# FPGA1_POWER.net
KiCad netlist of a schematic drawn in Altium Designer
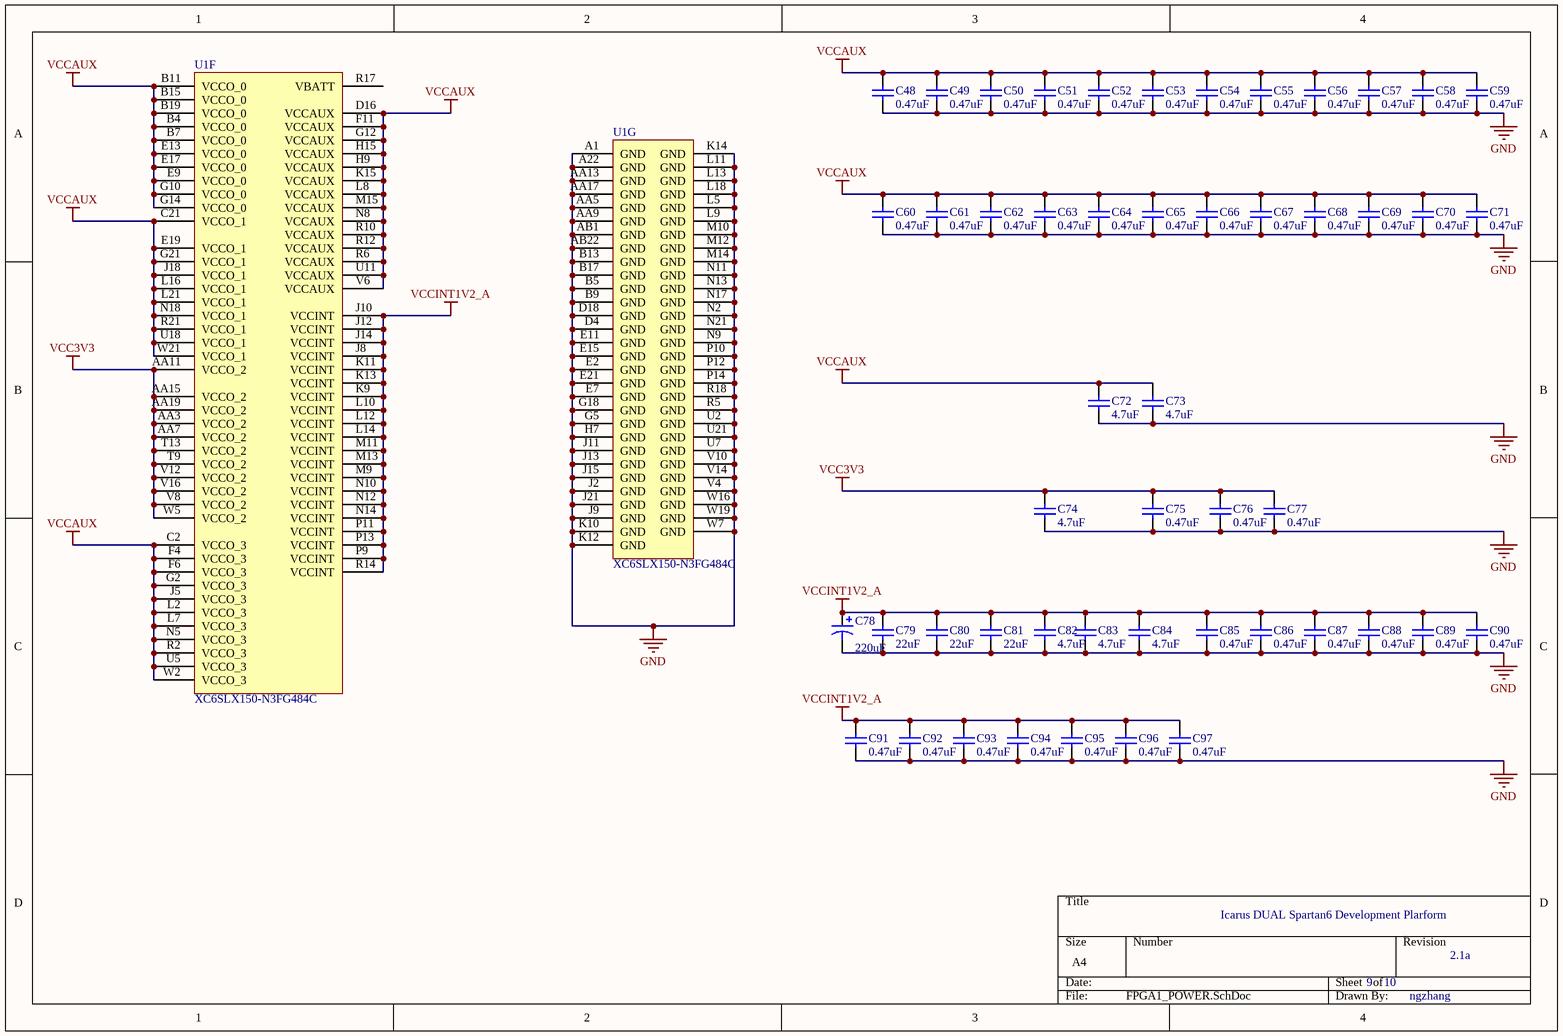
[diagram p0: FPGA1_POWER.SchDoc]

(export (version "E")
  (design (tool "Eeschema 10.0.6"))
  (components
    (comp (ref "C48")
      (value "0.47uF")
      (footprint "0402")
      (description "Capacitor (Semiconductor SIM Model)")
      (fields (field (name "PUBLISHER") "Altium Limited"))
      (libsource (lib "Miscellaneous Devices") (part "Cap Semi"))
    )
    (comp (ref "C49")
      (value "0.47uF")
      (footprint "0402")
      (description "Capacitor (Semiconductor SIM Model)")
      (fields (field (name "PUBLISHER") "Altium Limited"))
      (libsource (lib "Miscellaneous Devices") (part "Cap Semi"))
    )
    (comp (ref "C50")
      (value "0.47uF")
      (footprint "0402")
      (description "Capacitor (Semiconductor SIM Model)")
      (fields (field (name "PUBLISHER") "Altium Limited"))
      (libsource (lib "Miscellaneous Devices") (part "Cap Semi"))
    )
    (comp (ref "C51")
      (value "0.47uF")
      (footprint "0402")
      (description "Capacitor (Semiconductor SIM Model)")
      (fields (field (name "PUBLISHER") "Altium Limited"))
      (libsource (lib "Miscellaneous Devices") (part "Cap Semi"))
    )
    (comp (ref "C52")
      (value "0.47uF")
      (footprint "0402")
      (description "Capacitor (Semiconductor SIM Model)")
      (fields (field (name "PUBLISHER") "Altium Limited"))
      (libsource (lib "Miscellaneous Devices") (part "Cap Semi"))
    )
    (comp (ref "C53")
      (value "0.47uF")
      (footprint "0402")
      (description "Capacitor (Semiconductor SIM Model)")
      (fields (field (name "PUBLISHER") "Altium Limited"))
      (libsource (lib "Miscellaneous Devices") (part "Cap Semi"))
    )
    (comp (ref "C54")
      (value "0.47uF")
      (footprint "0402")
      (description "Capacitor (Semiconductor SIM Model)")
      (fields (field (name "PUBLISHER") "Altium Limited"))
      (libsource (lib "Miscellaneous Devices") (part "Cap Semi"))
    )
    (comp (ref "C55")
      (value "0.47uF")
      (footprint "0402")
      (description "Capacitor (Semiconductor SIM Model)")
      (fields (field (name "PUBLISHER") "Altium Limited"))
      (libsource (lib "Miscellaneous Devices") (part "Cap Semi"))
    )
    (comp (ref "C56")
      (value "0.47uF")
      (footprint "0402")
      (description "Capacitor (Semiconductor SIM Model)")
      (fields (field (name "PUBLISHER") "Altium Limited"))
      (libsource (lib "Miscellaneous Devices") (part "Cap Semi"))
    )
    (comp (ref "C57")
      (value "0.47uF")
      (footprint "0402")
      (description "Capacitor (Semiconductor SIM Model)")
      (fields (field (name "PUBLISHER") "Altium Limited"))
      (libsource (lib "Miscellaneous Devices") (part "Cap Semi"))
    )
    (comp (ref "C58")
      (value "0.47uF")
      (footprint "0402")
      (description "Capacitor (Semiconductor SIM Model)")
      (fields (field (name "PUBLISHER") "Altium Limited"))
      (libsource (lib "Miscellaneous Devices") (part "Cap Semi"))
    )
    (comp (ref "C59")
      (value "0.47uF")
      (footprint "0402")
      (description "Capacitor (Semiconductor SIM Model)")
      (fields (field (name "PUBLISHER") "Altium Limited"))
      (libsource (lib "Miscellaneous Devices") (part "Cap Semi"))
    )
    (comp (ref "C60")
      (value "0.47uF")
      (footprint "0402")
      (description "Capacitor (Semiconductor SIM Model)")
      (fields (field (name "PUBLISHER") "Altium Limited"))
      (libsource (lib "Miscellaneous Devices") (part "Cap Semi"))
    )
    (comp (ref "C61")
      (value "0.47uF")
      (footprint "0402")
      (description "Capacitor (Semiconductor SIM Model)")
      (fields (field (name "PUBLISHER") "Altium Limited"))
      (libsource (lib "Miscellaneous Devices") (part "Cap Semi"))
    )
    (comp (ref "C62")
      (value "0.47uF")
      (footprint "0402")
      (description "Capacitor (Semiconductor SIM Model)")
      (fields (field (name "PUBLISHER") "Altium Limited"))
      (libsource (lib "Miscellaneous Devices") (part "Cap Semi"))
    )
    (comp (ref "C63")
      (value "0.47uF")
      (footprint "0402")
      (description "Capacitor (Semiconductor SIM Model)")
      (fields (field (name "PUBLISHER") "Altium Limited"))
      (libsource (lib "Miscellaneous Devices") (part "Cap Semi"))
    )
    (comp (ref "C64")
      (value "0.47uF")
      (footprint "0402")
      (description "Capacitor (Semiconductor SIM Model)")
      (fields (field (name "PUBLISHER") "Altium Limited"))
      (libsource (lib "Miscellaneous Devices") (part "Cap Semi"))
    )
    (comp (ref "C65")
      (value "0.47uF")
      (footprint "0402")
      (description "Capacitor (Semiconductor SIM Model)")
      (fields (field (name "PUBLISHER") "Altium Limited"))
      (libsource (lib "Miscellaneous Devices") (part "Cap Semi"))
    )
    (comp (ref "C66")
      (value "0.47uF")
      (footprint "0402")
      (description "Capacitor (Semiconductor SIM Model)")
      (fields (field (name "PUBLISHER") "Altium Limited"))
      (libsource (lib "Miscellaneous Devices") (part "Cap Semi"))
    )
    (comp (ref "C67")
      (value "0.47uF")
      (footprint "0402")
      (description "Capacitor (Semiconductor SIM Model)")
      (fields (field (name "PUBLISHER") "Altium Limited"))
      (libsource (lib "Miscellaneous Devices") (part "Cap Semi"))
    )
    (comp (ref "C68")
      (value "0.47uF")
      (footprint "0402")
      (description "Capacitor (Semiconductor SIM Model)")
      (fields (field (name "PUBLISHER") "Altium Limited"))
      (libsource (lib "Miscellaneous Devices") (part "Cap Semi"))
    )
    (comp (ref "C69")
      (value "0.47uF")
      (footprint "0402")
      (description "Capacitor (Semiconductor SIM Model)")
      (fields (field (name "PUBLISHER") "Altium Limited"))
      (libsource (lib "Miscellaneous Devices") (part "Cap Semi"))
    )
    (comp (ref "C70")
      (value "0.47uF")
      (footprint "0402")
      (description "Capacitor (Semiconductor SIM Model)")
      (fields (field (name "PUBLISHER") "Altium Limited"))
      (libsource (lib "Miscellaneous Devices") (part "Cap Semi"))
    )
    (comp (ref "C71")
      (value "0.47uF")
      (footprint "0402")
      (description "Capacitor (Semiconductor SIM Model)")
      (fields (field (name "PUBLISHER") "Altium Limited"))
      (libsource (lib "Miscellaneous Devices") (part "Cap Semi"))
    )
    (comp (ref "C72")
      (value "4.7uF")
      (footprint "C0805")
      (description "Capacitor (Semiconductor SIM Model)")
      (fields (field (name "PUBLISHER") "Altium Limited"))
      (libsource (lib "Miscellaneous Devices") (part "Cap Semi"))
    )
    (comp (ref "C73")
      (value "4.7uF")
      (footprint "C0805")
      (description "Capacitor (Semiconductor SIM Model)")
      (fields (field (name "PUBLISHER") "Altium Limited"))
      (libsource (lib "Miscellaneous Devices") (part "Cap Semi"))
    )
    (comp (ref "C74")
      (value "4.7uF")
      (footprint "C0805")
      (description "Capacitor (Semiconductor SIM Model)")
      (fields (field (name "PUBLISHER") "Altium Limited"))
      (libsource (lib "Miscellaneous Devices") (part "Cap Semi"))
    )
    (comp (ref "C75")
      (value "0.47uF")
      (footprint "0402")
      (description "Capacitor (Semiconductor SIM Model)")
      (fields (field (name "PUBLISHER") "Altium Limited"))
      (libsource (lib "Miscellaneous Devices") (part "Cap Semi"))
    )
    (comp (ref "C76")
      (value "0.47uF")
      (footprint "0402")
      (description "Capacitor (Semiconductor SIM Model)")
      (fields (field (name "PUBLISHER") "Altium Limited"))
      (libsource (lib "Miscellaneous Devices") (part "Cap Semi"))
    )
    (comp (ref "C77")
      (value "0.47uF")
      (footprint "0402")
      (description "Capacitor (Semiconductor SIM Model)")
      (fields (field (name "PUBLISHER") "Altium Limited"))
      (libsource (lib "Miscellaneous Devices") (part "Cap Semi"))
    )
    (comp (ref "C78")
      (value "220uF")
      (footprint "D")
      (description "Polarized Capacitor (Surface Mount)")
      (fields (field (name "PUBLISHER") "Altium Limited"))
      (libsource (lib "Miscellaneous Devices") (part "Cap Pol3"))
    )
    (comp (ref "C79")
      (value "22uF")
      (footprint "C1206")
      (description "Capacitor (Semiconductor SIM Model)")
      (fields (field (name "PUBLISHER") "Altium Limited"))
      (libsource (lib "Miscellaneous Devices") (part "Cap Semi"))
    )
    (comp (ref "C80")
      (value "22uF")
      (footprint "C1206")
      (description "Capacitor (Semiconductor SIM Model)")
      (fields (field (name "PUBLISHER") "Altium Limited"))
      (libsource (lib "Miscellaneous Devices") (part "Cap Semi"))
    )
    (comp (ref "C81")
      (value "22uF")
      (footprint "C1206")
      (description "Capacitor (Semiconductor SIM Model)")
      (fields (field (name "PUBLISHER") "Altium Limited"))
      (libsource (lib "Miscellaneous Devices") (part "Cap Semi"))
    )
    (comp (ref "C82")
      (value "4.7uF")
      (footprint "C0805")
      (description "Capacitor (Semiconductor SIM Model)")
      (fields (field (name "PUBLISHER") "Altium Limited"))
      (libsource (lib "Miscellaneous Devices") (part "Cap Semi"))
    )
    (comp (ref "C83")
      (value "4.7uF")
      (footprint "C0805")
      (description "Capacitor (Semiconductor SIM Model)")
      (fields (field (name "PUBLISHER") "Altium Limited"))
      (libsource (lib "Miscellaneous Devices") (part "Cap Semi"))
    )
    (comp (ref "C84")
      (value "4.7uF")
      (footprint "C0805")
      (description "Capacitor (Semiconductor SIM Model)")
      (fields (field (name "PUBLISHER") "Altium Limited"))
      (libsource (lib "Miscellaneous Devices") (part "Cap Semi"))
    )
    (comp (ref "C85")
      (value "0.47uF")
      (footprint "0402")
      (description "Capacitor (Semiconductor SIM Model)")
      (fields (field (name "PUBLISHER") "Altium Limited"))
      (libsource (lib "Miscellaneous Devices") (part "Cap Semi"))
    )
    (comp (ref "C86")
      (value "0.47uF")
      (footprint "0402")
      (description "Capacitor (Semiconductor SIM Model)")
      (fields (field (name "PUBLISHER") "Altium Limited"))
      (libsource (lib "Miscellaneous Devices") (part "Cap Semi"))
    )
    (comp (ref "C87")
      (value "0.47uF")
      (footprint "0402")
      (description "Capacitor (Semiconductor SIM Model)")
      (fields (field (name "PUBLISHER") "Altium Limited"))
      (libsource (lib "Miscellaneous Devices") (part "Cap Semi"))
    )
    (comp (ref "C88")
      (value "0.47uF")
      (footprint "0402")
      (description "Capacitor (Semiconductor SIM Model)")
      (fields (field (name "PUBLISHER") "Altium Limited"))
      (libsource (lib "Miscellaneous Devices") (part "Cap Semi"))
    )
    (comp (ref "C89")
      (value "0.47uF")
      (footprint "0402")
      (description "Capacitor (Semiconductor SIM Model)")
      (fields (field (name "PUBLISHER") "Altium Limited"))
      (libsource (lib "Miscellaneous Devices") (part "Cap Semi"))
    )
    (comp (ref "C90")
      (value "0.47uF")
      (footprint "0402")
      (description "Capacitor (Semiconductor SIM Model)")
      (fields (field (name "PUBLISHER") "Altium Limited"))
      (libsource (lib "Miscellaneous Devices") (part "Cap Semi"))
    )
    (comp (ref "C91")
      (value "0.47uF")
      (footprint "0402")
      (description "Capacitor (Semiconductor SIM Model)")
      (fields (field (name "PUBLISHER") "Altium Limited"))
      (libsource (lib "Miscellaneous Devices") (part "Cap Semi"))
    )
    (comp (ref "C92")
      (value "0.47uF")
      (footprint "0402")
      (description "Capacitor (Semiconductor SIM Model)")
      (fields (field (name "PUBLISHER") "Altium Limited"))
      (libsource (lib "Miscellaneous Devices") (part "Cap Semi"))
    )
    (comp (ref "C93")
      (value "0.47uF")
      (footprint "0402")
      (description "Capacitor (Semiconductor SIM Model)")
      (fields (field (name "PUBLISHER") "Altium Limited"))
      (libsource (lib "Miscellaneous Devices") (part "Cap Semi"))
    )
    (comp (ref "C94")
      (value "0.47uF")
      (footprint "0402")
      (description "Capacitor (Semiconductor SIM Model)")
      (fields (field (name "PUBLISHER") "Altium Limited"))
      (libsource (lib "Miscellaneous Devices") (part "Cap Semi"))
    )
    (comp (ref "C95")
      (value "0.47uF")
      (footprint "0402")
      (description "Capacitor (Semiconductor SIM Model)")
      (fields (field (name "PUBLISHER") "Altium Limited"))
      (libsource (lib "Miscellaneous Devices") (part "Cap Semi"))
    )
    (comp (ref "C96")
      (value "0.47uF")
      (footprint "0402")
      (description "Capacitor (Semiconductor SIM Model)")
      (fields (field (name "PUBLISHER") "Altium Limited"))
      (libsource (lib "Miscellaneous Devices") (part "Cap Semi"))
    )
    (comp (ref "C97")
      (value "0.47uF")
      (footprint "0402")
      (description "Capacitor (Semiconductor SIM Model)")
      (fields (field (name "PUBLISHER") "Altium Limited"))
      (libsource (lib "Miscellaneous Devices") (part "Cap Semi"))
    )
    (comp (ref "U1")
      (value "XC6SLX150-N3FG484C")
      (footprint "FG484")
      (fields (field (name "PUBLISHER") "Altium Limited"))
      (libsource (lib "Xilinx Spartan-6") (part "XC6SLX150-N3FG484C"))
    )
  )
  (nets
    (net (code "1") (name "GND") (class "Default")
      (node (ref "C48") (pin "1") (pinfunction "1_1") (pintype "passive"))
      (node (ref "C49") (pin "1") (pinfunction "1_1") (pintype "passive"))
      (node (ref "C50") (pin "1") (pinfunction "1_1") (pintype "passive"))
      (node (ref "C51") (pin "1") (pinfunction "1_1") (pintype "passive"))
      (node (ref "C52") (pin "1") (pinfunction "1_1") (pintype "passive"))
      (node (ref "C53") (pin "1") (pinfunction "1_1") (pintype "passive"))
      (node (ref "C54") (pin "1") (pinfunction "1_1") (pintype "passive"))
      (node (ref "C55") (pin "1") (pinfunction "1_1") (pintype "passive"))
      (node (ref "C56") (pin "1") (pinfunction "1_1") (pintype "passive"))
      (node (ref "C57") (pin "1") (pinfunction "1_1") (pintype "passive"))
      (node (ref "C58") (pin "1") (pinfunction "1_1") (pintype "passive"))
      (node (ref "C59") (pin "1") (pinfunction "1_1") (pintype "passive"))
      (node (ref "C60") (pin "1") (pinfunction "1_1") (pintype "passive"))
      (node (ref "C61") (pin "1") (pinfunction "1_1") (pintype "passive"))
      (node (ref "C62") (pin "1") (pinfunction "1_1") (pintype "passive"))
      (node (ref "C63") (pin "1") (pinfunction "1_1") (pintype "passive"))
      (node (ref "C64") (pin "1") (pinfunction "1_1") (pintype "passive"))
      (node (ref "C65") (pin "1") (pinfunction "1_1") (pintype "passive"))
      (node (ref "C66") (pin "1") (pinfunction "1_1") (pintype "passive"))
      (node (ref "C67") (pin "1") (pinfunction "1_1") (pintype "passive"))
      (node (ref "C68") (pin "1") (pinfunction "1_1") (pintype "passive"))
      (node (ref "C69") (pin "1") (pinfunction "1_1") (pintype "passive"))
      (node (ref "C70") (pin "1") (pinfunction "1_1") (pintype "passive"))
      (node (ref "C71") (pin "1") (pinfunction "1_1") (pintype "passive"))
      (node (ref "C72") (pin "1") (pinfunction "1_1") (pintype "passive"))
      (node (ref "C73") (pin "1") (pinfunction "1_1") (pintype "passive"))
      (node (ref "C74") (pin "1") (pinfunction "1_1") (pintype "passive"))
      (node (ref "C75") (pin "1") (pinfunction "1_1") (pintype "passive"))
      (node (ref "C76") (pin "1") (pinfunction "1_1") (pintype "passive"))
      (node (ref "C77") (pin "1") (pinfunction "1_1") (pintype "passive"))
      (node (ref "C78") (pin "2") (pinfunction "2_2") (pintype "passive"))
      (node (ref "C79") (pin "1") (pinfunction "1_1") (pintype "passive"))
      (node (ref "C80") (pin "1") (pinfunction "1_1") (pintype "passive"))
      (node (ref "C81") (pin "1") (pinfunction "1_1") (pintype "passive"))
      (node (ref "C82") (pin "1") (pinfunction "1_1") (pintype "passive"))
      (node (ref "C83") (pin "1") (pinfunction "1_1") (pintype "passive"))
      (node (ref "C84") (pin "1") (pinfunction "1_1") (pintype "passive"))
      (node (ref "C85") (pin "1") (pinfunction "1_1") (pintype "passive"))
      (node (ref "C86") (pin "1") (pinfunction "1_1") (pintype "passive"))
      (node (ref "C87") (pin "1") (pinfunction "1_1") (pintype "passive"))
      (node (ref "C88") (pin "1") (pinfunction "1_1") (pintype "passive"))
      (node (ref "C89") (pin "1") (pinfunction "1_1") (pintype "passive"))
      (node (ref "C90") (pin "1") (pinfunction "1_1") (pintype "passive"))
      (node (ref "C91") (pin "1") (pinfunction "1_1") (pintype "passive"))
      (node (ref "C92") (pin "1") (pinfunction "1_1") (pintype "passive"))
      (node (ref "C93") (pin "1") (pinfunction "1_1") (pintype "passive"))
      (node (ref "C94") (pin "1") (pinfunction "1_1") (pintype "passive"))
      (node (ref "C95") (pin "1") (pinfunction "1_1") (pintype "passive"))
      (node (ref "C96") (pin "1") (pinfunction "1_1") (pintype "passive"))
      (node (ref "C97") (pin "1") (pinfunction "1_1") (pintype "passive"))
      (node (ref "U1") (pin "A1") (pinfunction "GND_A1") (pintype "power_in"))
      (node (ref "U1") (pin "A22") (pinfunction "GND_A22") (pintype "power_in"))
      (node (ref "U1") (pin "AA13") (pinfunction "GND_AA13") (pintype "power_in"))
      (node (ref "U1") (pin "AA17") (pinfunction "GND_AA17") (pintype "power_in"))
      (node (ref "U1") (pin "AA5") (pinfunction "GND_AA5") (pintype "power_in"))
      (node (ref "U1") (pin "AA9") (pinfunction "GND_AA9") (pintype "power_in"))
      (node (ref "U1") (pin "AB1") (pinfunction "GND_AB1") (pintype "power_in"))
      (node (ref "U1") (pin "AB22") (pinfunction "GND_AB22") (pintype "power_in"))
      (node (ref "U1") (pin "B13") (pinfunction "GND_B13") (pintype "power_in"))
      (node (ref "U1") (pin "B17") (pinfunction "GND_B17") (pintype "power_in"))
      (node (ref "U1") (pin "B5") (pinfunction "GND_B5") (pintype "power_in"))
      (node (ref "U1") (pin "B9") (pinfunction "GND_B9") (pintype "power_in"))
      (node (ref "U1") (pin "D18") (pinfunction "GND_D18") (pintype "power_in"))
      (node (ref "U1") (pin "D4") (pinfunction "GND_D4") (pintype "power_in"))
      (node (ref "U1") (pin "E11") (pinfunction "GND_E11") (pintype "power_in"))
      (node (ref "U1") (pin "E15") (pinfunction "GND_E15") (pintype "power_in"))
      (node (ref "U1") (pin "E2") (pinfunction "GND_E2") (pintype "power_in"))
      (node (ref "U1") (pin "E21") (pinfunction "GND_E21") (pintype "power_in"))
      (node (ref "U1") (pin "E7") (pinfunction "GND_E7") (pintype "power_in"))
      (node (ref "U1") (pin "G18") (pinfunction "GND_G18") (pintype "power_in"))
      (node (ref "U1") (pin "G5") (pinfunction "GND_G5") (pintype "power_in"))
      (node (ref "U1") (pin "H7") (pinfunction "GND_H7") (pintype "power_in"))
      (node (ref "U1") (pin "J11") (pinfunction "GND_J11") (pintype "power_in"))
      (node (ref "U1") (pin "J13") (pinfunction "GND_J13") (pintype "power_in"))
      (node (ref "U1") (pin "J15") (pinfunction "GND_J15") (pintype "power_in"))
      (node (ref "U1") (pin "J2") (pinfunction "GND_J2") (pintype "power_in"))
      (node (ref "U1") (pin "J21") (pinfunction "GND_J21") (pintype "power_in"))
      (node (ref "U1") (pin "J9") (pinfunction "GND_J9") (pintype "power_in"))
      (node (ref "U1") (pin "K10") (pinfunction "GND_K10") (pintype "power_in"))
      (node (ref "U1") (pin "K12") (pinfunction "GND_K12") (pintype "power_in"))
      (node (ref "U1") (pin "K14") (pinfunction "GND_K14") (pintype "power_in"))
      (node (ref "U1") (pin "L11") (pinfunction "GND_L11") (pintype "power_in"))
      (node (ref "U1") (pin "L13") (pinfunction "GND_L13") (pintype "power_in"))
      (node (ref "U1") (pin "L18") (pinfunction "GND_L18") (pintype "power_in"))
      (node (ref "U1") (pin "L5") (pinfunction "GND_L5") (pintype "power_in"))
      (node (ref "U1") (pin "L9") (pinfunction "GND_L9") (pintype "power_in"))
      (node (ref "U1") (pin "M10") (pinfunction "GND_M10") (pintype "power_in"))
      (node (ref "U1") (pin "M12") (pinfunction "GND_M12") (pintype "power_in"))
      (node (ref "U1") (pin "M14") (pinfunction "GND_M14") (pintype "power_in"))
      (node (ref "U1") (pin "N11") (pinfunction "GND_N11") (pintype "power_in"))
      (node (ref "U1") (pin "N13") (pinfunction "GND_N13") (pintype "power_in"))
      (node (ref "U1") (pin "N17") (pinfunction "GND_N17") (pintype "power_in"))
      (node (ref "U1") (pin "N2") (pinfunction "GND_N2") (pintype "power_in"))
      (node (ref "U1") (pin "N21") (pinfunction "GND_N21") (pintype "power_in"))
      (node (ref "U1") (pin "N9") (pinfunction "GND_N9") (pintype "power_in"))
      (node (ref "U1") (pin "P10") (pinfunction "GND_P10") (pintype "power_in"))
      (node (ref "U1") (pin "P12") (pinfunction "GND_P12") (pintype "power_in"))
      (node (ref "U1") (pin "P14") (pinfunction "GND_P14") (pintype "power_in"))
      (node (ref "U1") (pin "R18") (pinfunction "GND_R18") (pintype "power_in"))
      (node (ref "U1") (pin "R5") (pinfunction "GND_R5") (pintype "power_in"))
      (node (ref "U1") (pin "U2") (pinfunction "GND_U2") (pintype "power_in"))
      (node (ref "U1") (pin "U21") (pinfunction "GND_U21") (pintype "power_in"))
      (node (ref "U1") (pin "U7") (pinfunction "GND_U7") (pintype "power_in"))
      (node (ref "U1") (pin "V10") (pinfunction "GND_V10") (pintype "power_in"))
      (node (ref "U1") (pin "V14") (pinfunction "GND_V14") (pintype "power_in"))
      (node (ref "U1") (pin "V4") (pinfunction "GND_V4") (pintype "power_in"))
      (node (ref "U1") (pin "W16") (pinfunction "GND_W16") (pintype "power_in"))
      (node (ref "U1") (pin "W19") (pinfunction "GND_W19") (pintype "power_in"))
      (node (ref "U1") (pin "W7") (pinfunction "GND_W7") (pintype "power_in"))
    )
    (net (code "2") (name "VCC3V3") (class "Default")
      (node (ref "C74") (pin "2") (pinfunction "2_2") (pintype "passive"))
      (node (ref "C75") (pin "2") (pinfunction "2_2") (pintype "passive"))
      (node (ref "C76") (pin "2") (pinfunction "2_2") (pintype "passive"))
      (node (ref "C77") (pin "2") (pinfunction "2_2") (pintype "passive"))
      (node (ref "U1") (pin "AA11") (pinfunction "VCCO_2_AA11") (pintype "power_in"))
      (node (ref "U1") (pin "AA15") (pinfunction "VCCO_2_AA15") (pintype "power_in"))
      (node (ref "U1") (pin "AA19") (pinfunction "VCCO_2_AA19") (pintype "power_in"))
      (node (ref "U1") (pin "AA3") (pinfunction "VCCO_2_AA3") (pintype "power_in"))
      (node (ref "U1") (pin "AA7") (pinfunction "VCCO_2_AA7") (pintype "power_in"))
      (node (ref "U1") (pin "T13") (pinfunction "VCCO_2_T13") (pintype "power_in"))
      (node (ref "U1") (pin "T9") (pinfunction "VCCO_2_T9") (pintype "power_in"))
      (node (ref "U1") (pin "V12") (pinfunction "VCCO_2_V12") (pintype "power_in"))
      (node (ref "U1") (pin "V16") (pinfunction "VCCO_2_V16") (pintype "power_in"))
      (node (ref "U1") (pin "V8") (pinfunction "VCCO_2_V8") (pintype "power_in"))
      (node (ref "U1") (pin "W5") (pinfunction "VCCO_2_W5") (pintype "power_in"))
    )
    (net (code "3") (name "VCCAUX") (class "Default")
      (node (ref "C48") (pin "2") (pinfunction "2_2") (pintype "passive"))
      (node (ref "C49") (pin "2") (pinfunction "2_2") (pintype "passive"))
      (node (ref "C50") (pin "2") (pinfunction "2_2") (pintype "passive"))
      (node (ref "C51") (pin "2") (pinfunction "2_2") (pintype "passive"))
      (node (ref "C52") (pin "2") (pinfunction "2_2") (pintype "passive"))
      (node (ref "C53") (pin "2") (pinfunction "2_2") (pintype "passive"))
      (node (ref "C54") (pin "2") (pinfunction "2_2") (pintype "passive"))
      (node (ref "C55") (pin "2") (pinfunction "2_2") (pintype "passive"))
      (node (ref "C56") (pin "2") (pinfunction "2_2") (pintype "passive"))
      (node (ref "C57") (pin "2") (pinfunction "2_2") (pintype "passive"))
      (node (ref "C58") (pin "2") (pinfunction "2_2") (pintype "passive"))
      (node (ref "C59") (pin "2") (pinfunction "2_2") (pintype "passive"))
      (node (ref "C60") (pin "2") (pinfunction "2_2") (pintype "passive"))
      (node (ref "C61") (pin "2") (pinfunction "2_2") (pintype "passive"))
      (node (ref "C62") (pin "2") (pinfunction "2_2") (pintype "passive"))
      (node (ref "C63") (pin "2") (pinfunction "2_2") (pintype "passive"))
      (node (ref "C64") (pin "2") (pinfunction "2_2") (pintype "passive"))
      (node (ref "C65") (pin "2") (pinfunction "2_2") (pintype "passive"))
      (node (ref "C66") (pin "2") (pinfunction "2_2") (pintype "passive"))
      (node (ref "C67") (pin "2") (pinfunction "2_2") (pintype "passive"))
      (node (ref "C68") (pin "2") (pinfunction "2_2") (pintype "passive"))
      (node (ref "C69") (pin "2") (pinfunction "2_2") (pintype "passive"))
      (node (ref "C70") (pin "2") (pinfunction "2_2") (pintype "passive"))
      (node (ref "C71") (pin "2") (pinfunction "2_2") (pintype "passive"))
      (node (ref "C72") (pin "2") (pinfunction "2_2") (pintype "passive"))
      (node (ref "C73") (pin "2") (pinfunction "2_2") (pintype "passive"))
      (node (ref "U1") (pin "B11") (pinfunction "VCCO_0_B11") (pintype "power_in"))
      (node (ref "U1") (pin "B15") (pinfunction "VCCO_0_B15") (pintype "power_in"))
      (node (ref "U1") (pin "B19") (pinfunction "VCCO_0_B19") (pintype "power_in"))
      (node (ref "U1") (pin "B4") (pinfunction "VCCO_0_B4") (pintype "power_in"))
      (node (ref "U1") (pin "B7") (pinfunction "VCCO_0_B7") (pintype "power_in"))
      (node (ref "U1") (pin "C2") (pinfunction "VCCO_3_C2") (pintype "power_in"))
      (node (ref "U1") (pin "C21") (pinfunction "VCCO_1_C21") (pintype "power_in"))
      (node (ref "U1") (pin "D16") (pinfunction "VCCAUX_D16") (pintype "power_in"))
      (node (ref "U1") (pin "E13") (pinfunction "VCCO_0_E13") (pintype "power_in"))
      (node (ref "U1") (pin "E17") (pinfunction "VCCO_0_E17") (pintype "power_in"))
      (node (ref "U1") (pin "E19") (pinfunction "VCCO_1_E19") (pintype "power_in"))
      (node (ref "U1") (pin "E9") (pinfunction "VCCO_0_E9") (pintype "power_in"))
      (node (ref "U1") (pin "F11") (pinfunction "VCCAUX_F11") (pintype "power_in"))
      (node (ref "U1") (pin "F4") (pinfunction "VCCO_3_F4") (pintype "power_in"))
      (node (ref "U1") (pin "F6") (pinfunction "VCCO_3_F6") (pintype "power_in"))
      (node (ref "U1") (pin "G10") (pinfunction "VCCO_0_G10") (pintype "power_in"))
      (node (ref "U1") (pin "G12") (pinfunction "VCCAUX_G12") (pintype "power_in"))
      (node (ref "U1") (pin "G14") (pinfunction "VCCO_0_G14") (pintype "power_in"))
      (node (ref "U1") (pin "G2") (pinfunction "VCCO_3_G2") (pintype "power_in"))
      (node (ref "U1") (pin "G21") (pinfunction "VCCO_1_G21") (pintype "power_in"))
      (node (ref "U1") (pin "H15") (pinfunction "VCCAUX_H15") (pintype "power_in"))
      (node (ref "U1") (pin "H9") (pinfunction "VCCAUX_H9") (pintype "power_in"))
      (node (ref "U1") (pin "J18") (pinfunction "VCCO_1_J18") (pintype "power_in"))
      (node (ref "U1") (pin "J5") (pinfunction "VCCO_3_J5") (pintype "power_in"))
      (node (ref "U1") (pin "K15") (pinfunction "VCCAUX_K15") (pintype "power_in"))
      (node (ref "U1") (pin "L16") (pinfunction "VCCO_1_L16") (pintype "power_in"))
      (node (ref "U1") (pin "L2") (pinfunction "VCCO_3_L2") (pintype "power_in"))
      (node (ref "U1") (pin "L21") (pinfunction "VCCO_1_L21") (pintype "power_in"))
      (node (ref "U1") (pin "L7") (pinfunction "VCCO_3_L7") (pintype "power_in"))
      (node (ref "U1") (pin "L8") (pinfunction "VCCAUX_L8") (pintype "power_in"))
      (node (ref "U1") (pin "M15") (pinfunction "VCCAUX_M15") (pintype "power_in"))
      (node (ref "U1") (pin "N18") (pinfunction "VCCO_1_N18") (pintype "power_in"))
      (node (ref "U1") (pin "N5") (pinfunction "VCCO_3_N5") (pintype "power_in"))
      (node (ref "U1") (pin "N8") (pinfunction "VCCAUX_N8") (pintype "power_in"))
      (node (ref "U1") (pin "R10") (pinfunction "VCCAUX_R10") (pintype "power_in"))
      (node (ref "U1") (pin "R12") (pinfunction "VCCAUX_R12") (pintype "power_in"))
      (node (ref "U1") (pin "R2") (pinfunction "VCCO_3_R2") (pintype "power_in"))
      (node (ref "U1") (pin "R21") (pinfunction "VCCO_1_R21") (pintype "power_in"))
      (node (ref "U1") (pin "R6") (pinfunction "VCCAUX_R6") (pintype "power_in"))
      (node (ref "U1") (pin "U11") (pinfunction "VCCAUX_U11") (pintype "power_in"))
      (node (ref "U1") (pin "U18") (pinfunction "VCCO_1_U18") (pintype "power_in"))
      (node (ref "U1") (pin "U5") (pinfunction "VCCO_3_U5") (pintype "power_in"))
      (node (ref "U1") (pin "V6") (pinfunction "VCCAUX_V6") (pintype "power_in"))
      (node (ref "U1") (pin "W2") (pinfunction "VCCO_3_W2") (pintype "power_in"))
      (node (ref "U1") (pin "W21") (pinfunction "VCCO_1_W21") (pintype "power_in"))
    )
    (net (code "4") (name "VCCINT1V2_A") (class "Default")
      (node (ref "C78") (pin "1") (pinfunction "1_1") (pintype "passive"))
      (node (ref "C79") (pin "2") (pinfunction "2_2") (pintype "passive"))
      (node (ref "C80") (pin "2") (pinfunction "2_2") (pintype "passive"))
      (node (ref "C81") (pin "2") (pinfunction "2_2") (pintype "passive"))
      (node (ref "C82") (pin "2") (pinfunction "2_2") (pintype "passive"))
      (node (ref "C83") (pin "2") (pinfunction "2_2") (pintype "passive"))
      (node (ref "C84") (pin "2") (pinfunction "2_2") (pintype "passive"))
      (node (ref "C85") (pin "2") (pinfunction "2_2") (pintype "passive"))
      (node (ref "C86") (pin "2") (pinfunction "2_2") (pintype "passive"))
      (node (ref "C87") (pin "2") (pinfunction "2_2") (pintype "passive"))
      (node (ref "C88") (pin "2") (pinfunction "2_2") (pintype "passive"))
      (node (ref "C89") (pin "2") (pinfunction "2_2") (pintype "passive"))
      (node (ref "C90") (pin "2") (pinfunction "2_2") (pintype "passive"))
      (node (ref "C91") (pin "2") (pinfunction "2_2") (pintype "passive"))
      (node (ref "C92") (pin "2") (pinfunction "2_2") (pintype "passive"))
      (node (ref "C93") (pin "2") (pinfunction "2_2") (pintype "passive"))
      (node (ref "C94") (pin "2") (pinfunction "2_2") (pintype "passive"))
      (node (ref "C95") (pin "2") (pinfunction "2_2") (pintype "passive"))
      (node (ref "C96") (pin "2") (pinfunction "2_2") (pintype "passive"))
      (node (ref "C97") (pin "2") (pinfunction "2_2") (pintype "passive"))
      (node (ref "U1") (pin "J10") (pinfunction "VCCINT_J10") (pintype "power_in"))
      (node (ref "U1") (pin "J12") (pinfunction "VCCINT_J12") (pintype "power_in"))
      (node (ref "U1") (pin "J14") (pinfunction "VCCINT_J14") (pintype "power_in"))
      (node (ref "U1") (pin "J8") (pinfunction "VCCINT_J8") (pintype "power_in"))
      (node (ref "U1") (pin "K11") (pinfunction "VCCINT_K11") (pintype "power_in"))
      (node (ref "U1") (pin "K13") (pinfunction "VCCINT_K13") (pintype "power_in"))
      (node (ref "U1") (pin "K9") (pinfunction "VCCINT_K9") (pintype "power_in"))
      (node (ref "U1") (pin "L10") (pinfunction "VCCINT_L10") (pintype "power_in"))
      (node (ref "U1") (pin "L12") (pinfunction "VCCINT_L12") (pintype "power_in"))
      (node (ref "U1") (pin "L14") (pinfunction "VCCINT_L14") (pintype "power_in"))
      (node (ref "U1") (pin "M11") (pinfunction "VCCINT_M11") (pintype "power_in"))
      (node (ref "U1") (pin "M13") (pinfunction "VCCINT_M13") (pintype "power_in"))
      (node (ref "U1") (pin "M9") (pinfunction "VCCINT_M9") (pintype "power_in"))
      (node (ref "U1") (pin "N10") (pinfunction "VCCINT_N10") (pintype "power_in"))
      (node (ref "U1") (pin "N12") (pinfunction "VCCINT_N12") (pintype "power_in"))
      (node (ref "U1") (pin "N14") (pinfunction "VCCINT_N14") (pintype "power_in"))
      (node (ref "U1") (pin "P11") (pinfunction "VCCINT_P11") (pintype "power_in"))
      (node (ref "U1") (pin "P13") (pinfunction "VCCINT_P13") (pintype "power_in"))
      (node (ref "U1") (pin "P9") (pinfunction "VCCINT_P9") (pintype "power_in"))
      (node (ref "U1") (pin "R14") (pinfunction "VCCINT_R14") (pintype "power_in"))
    )
    (net (code "5") (name "unconnected-(U1F-VBATT-PadR17)") (class "Default")
      (node (ref "U1") (pin "R17") (pinfunction "VBATT_R17") (pintype "power_in"))
    )
  )
)
